# SOS-Leak-Sensor.net
KiCad netlist of a schematic drawn in EAGLE
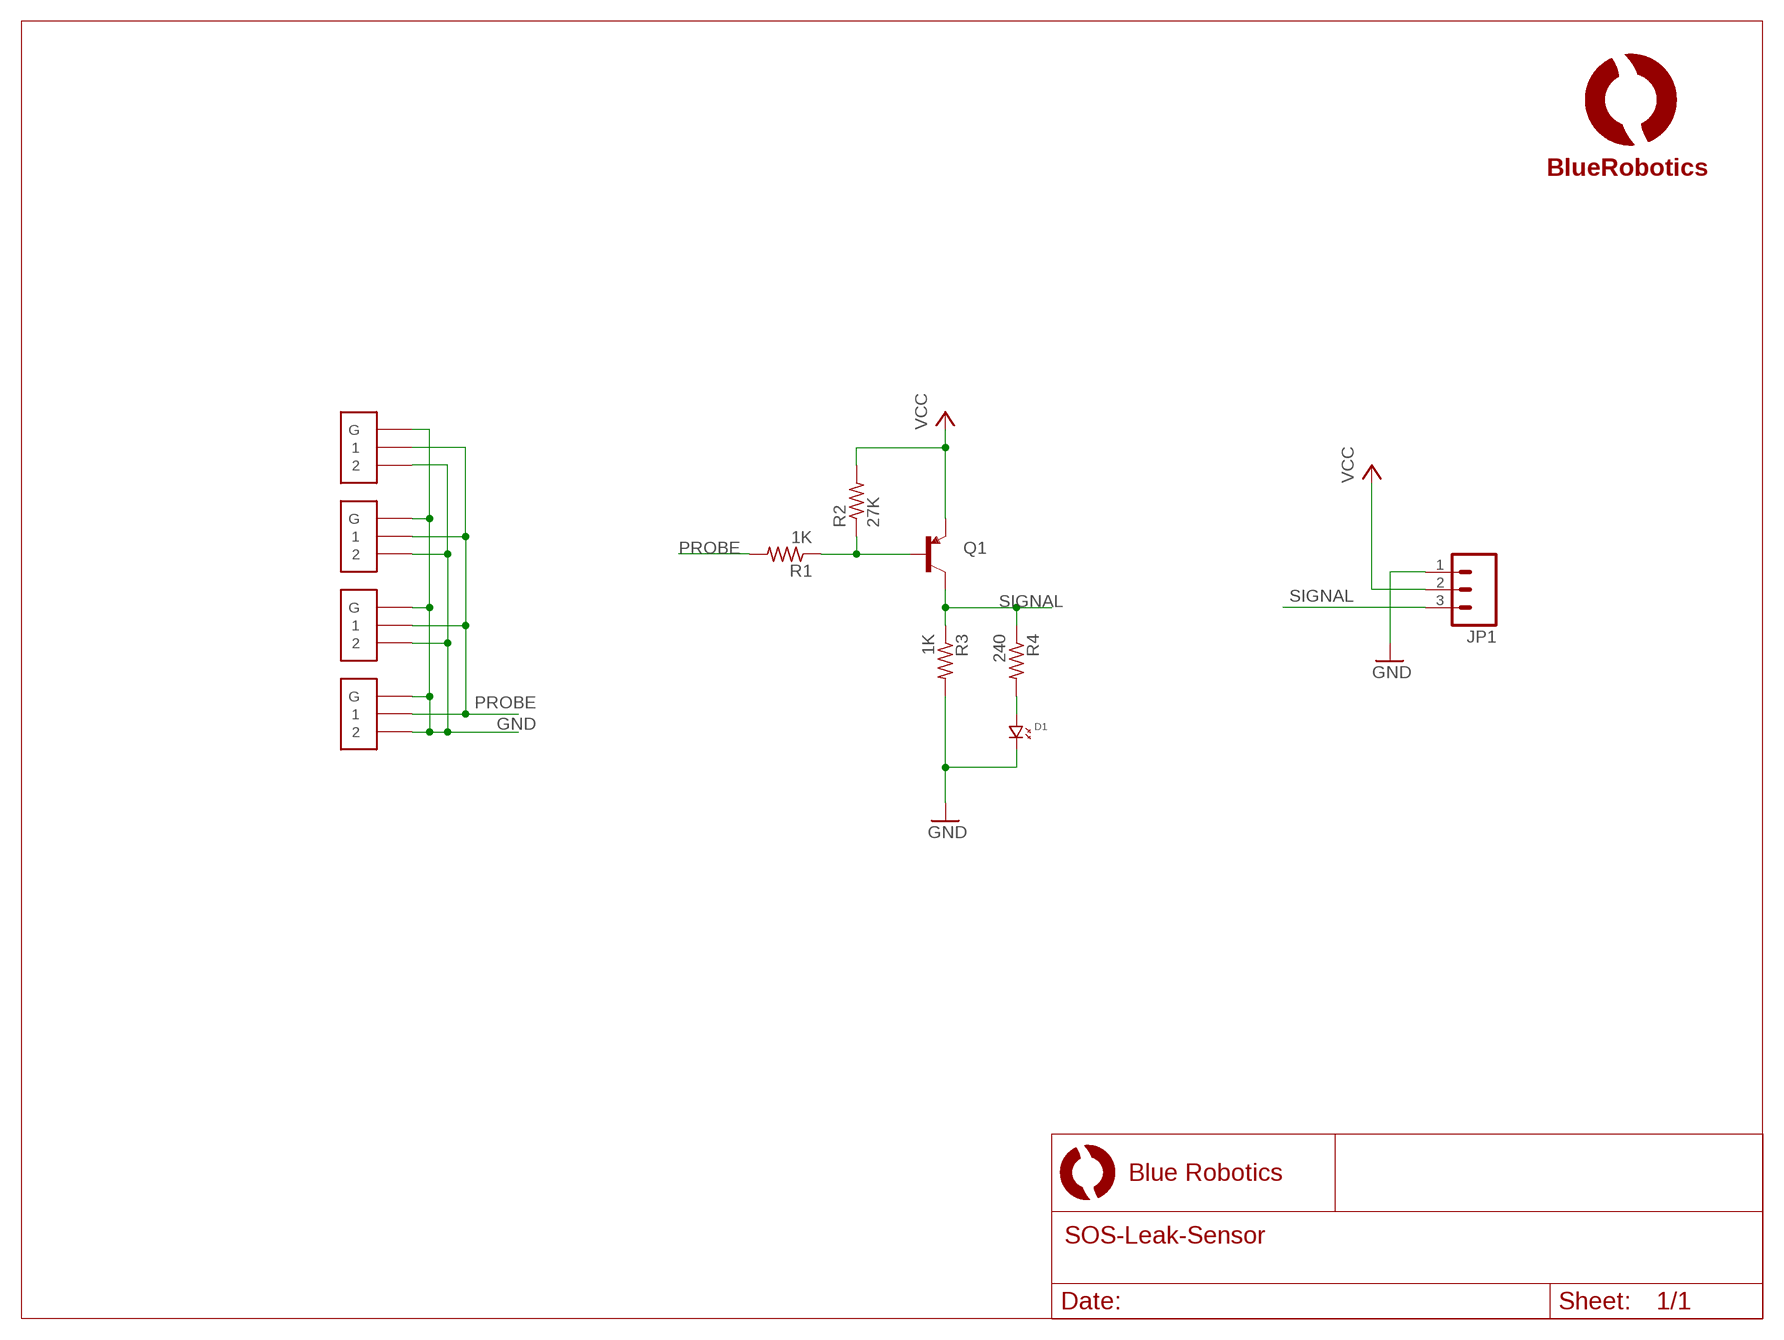
[diagram p0: schematic, sheet 1]

(export (version "E")
  (design (tool "Eeschema 10.0.6"))
  (components
    (comp (ref "D1")
      (value "LED.0805")
      (footprint "eagle-import:0805.LED")
      (libsource (lib "eagle-import") (part "LED.0805"))
    )
    (comp (ref "JP1")
      (value "M03PTH")
      (footprint "eagle-import:1X03")
      (libsource (lib "eagle-import") (part "M03PTH"))
    )
    (comp (ref "Q1")
      (value "TRANSISTOR_PNPSMD")
      (footprint "eagle-import:SOT23-3")
      (libsource (lib "eagle-import") (part "TRANSISTOR_PNPSMD"))
    )
    (comp (ref "R1")
      (value "1K")
      (footprint "eagle-import:R0603")
      (libsource (lib "eagle-import") (part "R-US_R0603"))
    )
    (comp (ref "R2")
      (value "27K")
      (footprint "eagle-import:R0603")
      (libsource (lib "eagle-import") (part "R-US_R0603"))
    )
    (comp (ref "R3")
      (value "1K")
      (footprint "eagle-import:R0603")
      (libsource (lib "eagle-import") (part "R-US_R0603"))
    )
    (comp (ref "R4")
      (value "240")
      (footprint "eagle-import:R0603")
      (libsource (lib "eagle-import") (part "R-US_R0603"))
    )
    (comp (ref "U$1")
      (value "JSH-GH-2VERT")
      (footprint "eagle-import:JST-GH-TOP-2")
      (libsource (lib "eagle-import") (part "JSH-GH-2VERT"))
    )
    (comp (ref "U$2")
      (value "JSH-GH-2VERT")
      (footprint "eagle-import:JST-GH-TOP-2")
      (libsource (lib "eagle-import") (part "JSH-GH-2VERT"))
    )
    (comp (ref "U$3")
      (value "JSH-GH-2VERT")
      (footprint "eagle-import:JST-GH-TOP-2")
      (libsource (lib "eagle-import") (part "JSH-GH-2VERT"))
    )
    (comp (ref "U$4")
      (value "JSH-GH-2VERT")
      (footprint "eagle-import:JST-GH-TOP-2")
      (libsource (lib "eagle-import") (part "JSH-GH-2VERT"))
    )
    (comp (ref "U$7")
      (value "LOGOBR-LOGO-S")
      (footprint "eagle-import:BR-LOGO-SMALL")
      (libsource (lib "eagle-import") (part "LOGOBR-LOGO-S"))
    )
  )
  (nets
    (net (code "1") (name "/PROBE") (class "Default")
      (node (ref "R1") (pin "2") (pinfunction "2_2") (pintype "passive"))
      (node (ref "U$1") (pin "1") (pinfunction "1_1") (pintype "bidirectional"))
      (node (ref "U$2") (pin "1") (pinfunction "1_1") (pintype "bidirectional"))
      (node (ref "U$3") (pin "1") (pinfunction "1_1") (pintype "bidirectional"))
      (node (ref "U$4") (pin "1") (pinfunction "1_1") (pintype "bidirectional"))
    )
    (net (code "2") (name "/SIGNAL") (class "Default")
      (node (ref "JP1") (pin "3") (pinfunction "3_3") (pintype "passive"))
      (node (ref "Q1") (pin "3") (pinfunction "C_3") (pintype "passive"))
      (node (ref "R3") (pin "1") (pinfunction "1_1") (pintype "passive"))
      (node (ref "R4") (pin "1") (pinfunction "1_1") (pintype "passive"))
    )
    (net (code "3") (name "GND") (class "Default")
      (node (ref "D1") (pin "P$2") (pinfunction "2_P$2") (pintype "bidirectional"))
      (node (ref "JP1") (pin "1") (pinfunction "1_1") (pintype "passive"))
      (node (ref "R3") (pin "2") (pinfunction "2_2") (pintype "passive"))
      (node (ref "U$1") (pin "2") (pinfunction "2_2") (pintype "bidirectional"))
      (node (ref "U$1") (pin "MECH1") (pinfunction "G_MECH1") (pintype "bidirectional"))
      (node (ref "U$1") (pin "MECH2") (pinfunction "G_MECH2") (pintype "bidirectional"))
      (node (ref "U$2") (pin "2") (pinfunction "2_2") (pintype "bidirectional"))
      (node (ref "U$2") (pin "MECH1") (pinfunction "G_MECH1") (pintype "bidirectional"))
      (node (ref "U$2") (pin "MECH2") (pinfunction "G_MECH2") (pintype "bidirectional"))
      (node (ref "U$3") (pin "2") (pinfunction "2_2") (pintype "bidirectional"))
      (node (ref "U$3") (pin "MECH1") (pinfunction "G_MECH1") (pintype "bidirectional"))
      (node (ref "U$3") (pin "MECH2") (pinfunction "G_MECH2") (pintype "bidirectional"))
      (node (ref "U$4") (pin "2") (pinfunction "2_2") (pintype "bidirectional"))
      (node (ref "U$4") (pin "MECH1") (pinfunction "G_MECH1") (pintype "bidirectional"))
      (node (ref "U$4") (pin "MECH2") (pinfunction "G_MECH2") (pintype "bidirectional"))
    )
    (net (code "4") (name "Net-(D1-1)") (class "Default")
      (node (ref "D1") (pin "P$1") (pinfunction "1_P$1") (pintype "bidirectional"))
      (node (ref "R4") (pin "2") (pinfunction "2_2") (pintype "passive"))
    )
    (net (code "5") (name "Net-(Q1-B)") (class "Default")
      (node (ref "Q1") (pin "1") (pinfunction "B_1") (pintype "passive"))
      (node (ref "R1") (pin "1") (pinfunction "1_1") (pintype "passive"))
      (node (ref "R2") (pin "1") (pinfunction "1_1") (pintype "passive"))
    )
    (net (code "6") (name "VCC") (class "Default")
      (node (ref "JP1") (pin "2") (pinfunction "2_2") (pintype "passive"))
      (node (ref "Q1") (pin "2") (pinfunction "E_2") (pintype "passive"))
      (node (ref "R2") (pin "2") (pinfunction "2_2") (pintype "passive"))
    )
  )
)
